# Connector.net
KiCad netlist of a schematic drawn in EAGLE
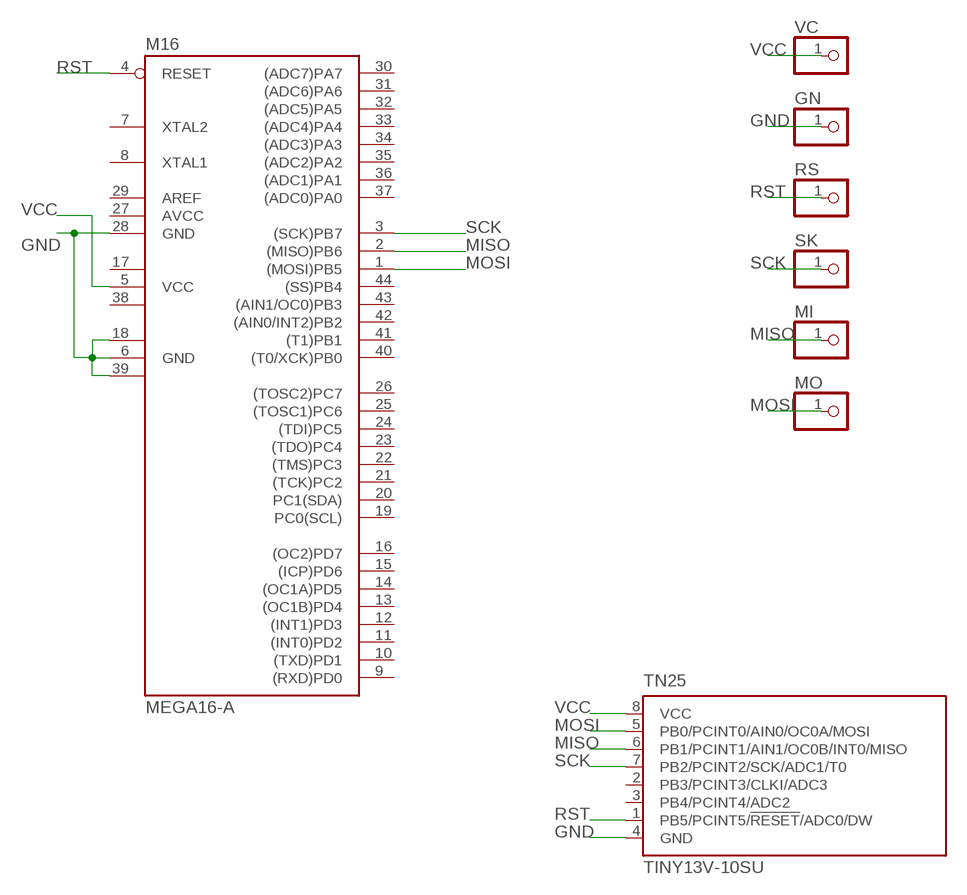
[diagram p0: schematic, sheet 1]

(export (version "E")
  (design (tool "Eeschema 10.0.6"))
  (components
    (comp (ref "GN")
      (value "PINHD-1X1")
      (footprint "eagle-import:1X01")
      (libsource (lib "eagle-import") (part "PINHD-1X1"))
    )
    (comp (ref "M16")
      (value "MEGA16-A")
      (footprint "eagle-import:TQFP44")
      (fields (field (name "MPN") "ATMEGA16-16AU"))
      (libsource (lib "eagle-import") (part "MEGA16-A"))
    )
    (comp (ref "MI")
      (value "PINHD-1X1")
      (footprint "eagle-import:1X01")
      (libsource (lib "eagle-import") (part "PINHD-1X1"))
    )
    (comp (ref "MO")
      (value "PINHD-1X1")
      (footprint "eagle-import:1X01")
      (libsource (lib "eagle-import") (part "PINHD-1X1"))
    )
    (comp (ref "RS")
      (value "PINHD-1X1")
      (footprint "eagle-import:1X01")
      (libsource (lib "eagle-import") (part "PINHD-1X1"))
    )
    (comp (ref "SK")
      (value "PINHD-1X1")
      (footprint "eagle-import:1X01")
      (libsource (lib "eagle-import") (part "PINHD-1X1"))
    )
    (comp (ref "TN25")
      (value "TINY13V-10SU")
      (footprint "eagle-import:8S2")
      (fields (field (name "MPN") "ATTINY13V-10SU"))
      (libsource (lib "eagle-import") (part "TINY13SUV-10"))
    )
    (comp (ref "VC")
      (value "PINHD-1X1")
      (footprint "eagle-import:1X01")
      (libsource (lib "eagle-import") (part "PINHD-1X1"))
    )
  )
  (nets
    (net (code "1") (name "/AVCC") (class "Default")
      (node (ref "M16") (pin "27") (pinfunction "AVCC_27") (pintype "power_in"))
    )
    (net (code "2") (name "/GND") (class "Default")
      (node (ref "GN") (pin "1") (pinfunction "1_1") (pintype "passive"))
      (node (ref "M16") (pin "18") (pinfunction "GND1_18") (pintype "power_in"))
      (node (ref "M16") (pin "28") (pinfunction "GND_28") (pintype "power_in"))
      (node (ref "M16") (pin "39") (pinfunction "GND2_39") (pintype "power_in"))
      (node (ref "M16") (pin "6") (pinfunction "GND_6") (pintype "power_in"))
      (node (ref "TN25") (pin "4") (pinfunction "GND_4") (pintype "power_in"))
    )
    (net (code "3") (name "/MISO") (class "Default")
      (node (ref "M16") (pin "2") (pinfunction "(MISO)PB6_2") (pintype "bidirectional"))
      (node (ref "MI") (pin "1") (pinfunction "1_1") (pintype "passive"))
      (node (ref "TN25") (pin "6") (pinfunction "PB1/PCINT1/AIN1/OC0B/INT0/MISO_6") (pintype "bidirectional"))
    )
    (net (code "4") (name "/MOSI") (class "Default")
      (node (ref "M16") (pin "1") (pinfunction "(MOSI)PB5_1") (pintype "bidirectional"))
      (node (ref "MO") (pin "1") (pinfunction "1_1") (pintype "passive"))
      (node (ref "TN25") (pin "5") (pinfunction "PB0/PCINT0/AIN0/OC0A/MOSI_5") (pintype "bidirectional"))
    )
    (net (code "5") (name "/RST") (class "Default")
      (node (ref "M16") (pin "4") (pinfunction "RESET_4") (pintype "input"))
      (node (ref "RS") (pin "1") (pinfunction "1_1") (pintype "passive"))
      (node (ref "TN25") (pin "1") (pinfunction "PB5/PCINT5/~{RESET}/ADC0/DW_1") (pintype "bidirectional"))
    )
    (net (code "6") (name "/SCK") (class "Default")
      (node (ref "M16") (pin "3") (pinfunction "(SCK)PB7_3") (pintype "bidirectional"))
      (node (ref "SK") (pin "1") (pinfunction "1_1") (pintype "passive"))
      (node (ref "TN25") (pin "7") (pinfunction "PB2/PCINT2/SCK/ADC1/T0_7") (pintype "bidirectional"))
    )
    (net (code "7") (name "/VCC") (class "Default")
      (node (ref "M16") (pin "5") (pinfunction "VCC_5") (pintype "power_in"))
      (node (ref "TN25") (pin "8") (pinfunction "VCC_8") (pintype "power_in"))
      (node (ref "VC") (pin "1") (pinfunction "1_1") (pintype "passive"))
    )
    (net (code "8") (name "/VCC1") (class "Default")
      (node (ref "M16") (pin "17") (pinfunction "VCC1_17") (pintype "power_in"))
    )
    (net (code "9") (name "/VCC2") (class "Default")
      (node (ref "M16") (pin "38") (pinfunction "VCC2_38") (pintype "power_in"))
    )
    (net (code "10") (name "unconnected-(M16-(ADC0)PA0-Pad37)") (class "Default")
      (node (ref "M16") (pin "37") (pinfunction "(ADC0)PA0_37") (pintype "bidirectional"))
    )
    (net (code "11") (name "unconnected-(M16-(ADC1)PA1-Pad36)") (class "Default")
      (node (ref "M16") (pin "36") (pinfunction "(ADC1)PA1_36") (pintype "bidirectional"))
    )
    (net (code "12") (name "unconnected-(M16-(ADC2)PA2-Pad35)") (class "Default")
      (node (ref "M16") (pin "35") (pinfunction "(ADC2)PA2_35") (pintype "bidirectional"))
    )
    (net (code "13") (name "unconnected-(M16-(ADC3)PA3-Pad34)") (class "Default")
      (node (ref "M16") (pin "34") (pinfunction "(ADC3)PA3_34") (pintype "bidirectional"))
    )
    (net (code "14") (name "unconnected-(M16-(ADC4)PA4-Pad33)") (class "Default")
      (node (ref "M16") (pin "33") (pinfunction "(ADC4)PA4_33") (pintype "bidirectional"))
    )
    (net (code "15") (name "unconnected-(M16-(ADC5)PA5-Pad32)") (class "Default")
      (node (ref "M16") (pin "32") (pinfunction "(ADC5)PA5_32") (pintype "bidirectional"))
    )
    (net (code "16") (name "unconnected-(M16-(ADC6)PA6-Pad31)") (class "Default")
      (node (ref "M16") (pin "31") (pinfunction "(ADC6)PA6_31") (pintype "bidirectional"))
    )
    (net (code "17") (name "unconnected-(M16-(ADC7)PA7-Pad30)") (class "Default")
      (node (ref "M16") (pin "30") (pinfunction "(ADC7)PA7_30") (pintype "bidirectional"))
    )
    (net (code "18") (name "unconnected-(M16-(AIN0{slash}INT2)PB2-Pad42)") (class "Default")
      (node (ref "M16") (pin "42") (pinfunction "(AIN0/INT2)PB2_42") (pintype "bidirectional"))
    )
    (net (code "19") (name "unconnected-(M16-(AIN1{slash}OC0)PB3-Pad43)") (class "Default")
      (node (ref "M16") (pin "43") (pinfunction "(AIN1/OC0)PB3_43") (pintype "bidirectional"))
    )
    (net (code "20") (name "unconnected-(M16-(ICP)PD6-Pad15)") (class "Default")
      (node (ref "M16") (pin "15") (pinfunction "(ICP)PD6_15") (pintype "bidirectional"))
    )
    (net (code "21") (name "unconnected-(M16-(INT0)PD2-Pad11)") (class "Default")
      (node (ref "M16") (pin "11") (pinfunction "(INT0)PD2_11") (pintype "bidirectional"))
    )
    (net (code "22") (name "unconnected-(M16-(INT1)PD3-Pad12)") (class "Default")
      (node (ref "M16") (pin "12") (pinfunction "(INT1)PD3_12") (pintype "bidirectional"))
    )
    (net (code "23") (name "unconnected-(M16-(OC1A)PD5-Pad14)") (class "Default")
      (node (ref "M16") (pin "14") (pinfunction "(OC1A)PD5_14") (pintype "bidirectional"))
    )
    (net (code "24") (name "unconnected-(M16-(OC1B)PD4-Pad13)") (class "Default")
      (node (ref "M16") (pin "13") (pinfunction "(OC1B)PD4_13") (pintype "bidirectional"))
    )
    (net (code "25") (name "unconnected-(M16-(OC2)PD7-Pad16)") (class "Default")
      (node (ref "M16") (pin "16") (pinfunction "(OC2)PD7_16") (pintype "bidirectional"))
    )
    (net (code "26") (name "unconnected-(M16-(RXD)PD0-Pad9)") (class "Default")
      (node (ref "M16") (pin "9") (pinfunction "(RXD)PD0_9") (pintype "bidirectional"))
    )
    (net (code "27") (name "unconnected-(M16-(SS)PB4-Pad44)") (class "Default")
      (node (ref "M16") (pin "44") (pinfunction "(SS)PB4_44") (pintype "bidirectional"))
    )
    (net (code "28") (name "unconnected-(M16-(T0{slash}XCK)PB0-Pad40)") (class "Default")
      (node (ref "M16") (pin "40") (pinfunction "(T0/XCK)PB0_40") (pintype "bidirectional"))
    )
    (net (code "29") (name "unconnected-(M16-(T1)PB1-Pad41)") (class "Default")
      (node (ref "M16") (pin "41") (pinfunction "(T1)PB1_41") (pintype "bidirectional"))
    )
    (net (code "30") (name "unconnected-(M16-(TCK)PC2-Pad21)") (class "Default")
      (node (ref "M16") (pin "21") (pinfunction "(TCK)PC2_21") (pintype "bidirectional"))
    )
    (net (code "31") (name "unconnected-(M16-(TDI)PC5-Pad24)") (class "Default")
      (node (ref "M16") (pin "24") (pinfunction "(TDI)PC5_24") (pintype "bidirectional"))
    )
    (net (code "32") (name "unconnected-(M16-(TDO)PC4-Pad23)") (class "Default")
      (node (ref "M16") (pin "23") (pinfunction "(TDO)PC4_23") (pintype "bidirectional"))
    )
    (net (code "33") (name "unconnected-(M16-(TMS)PC3-Pad22)") (class "Default")
      (node (ref "M16") (pin "22") (pinfunction "(TMS)PC3_22") (pintype "bidirectional"))
    )
    (net (code "34") (name "unconnected-(M16-(TOSC1)PC6-Pad25)") (class "Default")
      (node (ref "M16") (pin "25") (pinfunction "(TOSC1)PC6_25") (pintype "bidirectional"))
    )
    (net (code "35") (name "unconnected-(M16-(TOSC2)PC7-Pad26)") (class "Default")
      (node (ref "M16") (pin "26") (pinfunction "(TOSC2)PC7_26") (pintype "bidirectional"))
    )
    (net (code "36") (name "unconnected-(M16-(TXD)PD1-Pad10)") (class "Default")
      (node (ref "M16") (pin "10") (pinfunction "(TXD)PD1_10") (pintype "bidirectional"))
    )
    (net (code "37") (name "unconnected-(M16-AREF-Pad29)") (class "Default")
      (node (ref "M16") (pin "29") (pinfunction "AREF_29") (pintype "passive"))
    )
    (net (code "38") (name "unconnected-(M16-PC0(SCL)-Pad19)") (class "Default")
      (node (ref "M16") (pin "19") (pinfunction "PC0(SCL)_19") (pintype "bidirectional"))
    )
    (net (code "39") (name "unconnected-(M16-PC1(SDA)-Pad20)") (class "Default")
      (node (ref "M16") (pin "20") (pinfunction "PC1(SDA)_20") (pintype "bidirectional"))
    )
    (net (code "40") (name "unconnected-(M16-XTAL1-Pad8)") (class "Default")
      (node (ref "M16") (pin "8") (pinfunction "XTAL1_8") (pintype "bidirectional"))
    )
    (net (code "41") (name "unconnected-(M16-XTAL2-Pad7)") (class "Default")
      (node (ref "M16") (pin "7") (pinfunction "XTAL2_7") (pintype "bidirectional"))
    )
    (net (code "42") (name "unconnected-(TN25-PB3{slash}PCINT3{slash}CLKI{slash}ADC3-Pad2)") (class "Default")
      (node (ref "TN25") (pin "2") (pinfunction "PB3/PCINT3/CLKI/ADC3_2") (pintype "bidirectional"))
    )
    (net (code "43") (name "unconnected-(TN25-PB4{slash}PCINT4{slash}ADC2-Pad3)") (class "Default")
      (node (ref "TN25") (pin "3") (pinfunction "PB4/PCINT4/ADC2_3") (pintype "bidirectional"))
    )
  )
)
